# Power3V3.net
KiCad netlist of a schematic drawn in Altium Designer
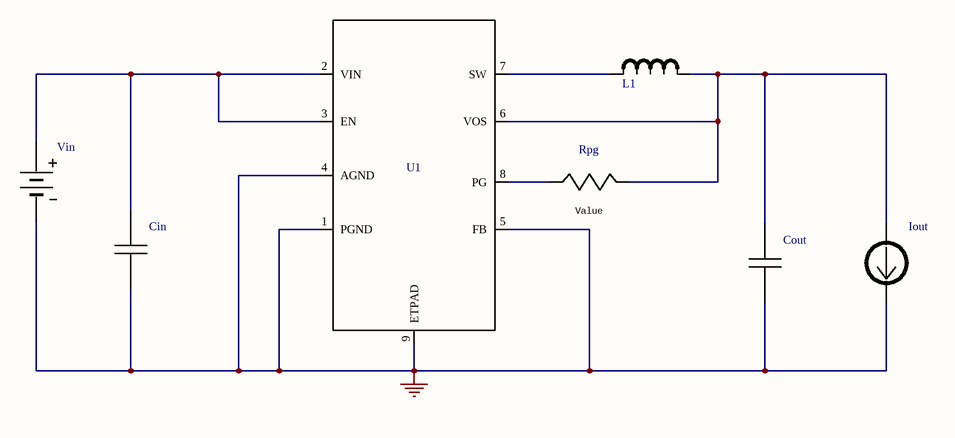
[diagram p0: Power3V3.SchDoc]

(export (version "E")
  (design (tool "Eeschema 10.0.6"))
  (components
    (comp (ref "Cin")
      (value "GRM219R61E106KA1")
      (footprint "0805")
      (description "Imported")
      (fields (field (name "MANUFACTURER_PART_NUMBER") "GRM219R61E106KA12"))
      (libsource (lib "TI WEBENCH") (part "GRM219R61E106KA1"))
    )
    (comp (ref "Cout")
      (value "GRM31CR70J226KE1")
      (footprint "1206")
      (description "Imported")
      (fields (field (name "MANUFACTURER_PART_NUMBER") "GRM31CR70J226KE19L"))
      (libsource (lib "TI WEBENCH") (part "GRM31CR70J226KE1"))
    )
    (comp (ref "Iout")
      (value "WB_CURRENT_LOAD")
      (description "Imported")
      (libsource (lib "TI WEBENCH") (part "WB_CURRENT_LOAD"))
    )
    (comp (ref "L1")
      (value "VLF252015MT-2R2M")
      (footprint "VLF252015MT")
      (description "Imported")
      (fields (field (name "MANUFACTURER_PART_NUMBER") "'VLF252015MT-2R2M'"))
      (libsource (lib "TI WEBENCH") (part "VLF252015MT-2R2M"))
    )
    (comp (ref "Rpg")
      (value "Value")
      (footprint "0402")
      (description "Imported")
      (fields (field (name "MANUFACTURER_PART_NUMBER") "CRCW0402100KFKED"))
      (libsource (lib "TI WEBENCH") (part "CRCW0402100KFKED"))
    )
    (comp (ref "U1")
      (value "TPS62172DSGR")
      (footprint "S-PWSON-N8")
      (description "Imported")
      (libsource (lib "TI WEBENCH") (part "TPS62172DSGR"))
    )
    (comp (ref "Vin")
      (value "WB_BATTERY")
      (description "Imported")
      (libsource (lib "TI WEBENCH") (part "WB_BATTERY"))
    )
  )
  (nets
    (net (code "1") (name "0") (class "Default")
      (node (ref "Cin") (pin "2") (pinfunction "2_2") (pintype "passive"))
      (node (ref "Cout") (pin "2") (pinfunction "2_2") (pintype "passive"))
      (node (ref "Iout") (pin "2") (pinfunction "-_2") (pintype "passive"))
      (node (ref "U1") (pin "1") (pinfunction "PGND_1") (pintype "passive"))
      (node (ref "U1") (pin "4") (pinfunction "AGND_4") (pintype "passive"))
      (node (ref "U1") (pin "5") (pinfunction "FB_5") (pintype "passive"))
      (node (ref "U1") (pin "9") (pinfunction "ETPAD_9") (pintype "passive"))
      (node (ref "Vin") (pin "2") (pinfunction "-_2") (pintype "passive"))
    )
    (net (code "2") (name "Net-(Iout-+)") (class "Default")
      (node (ref "Cout") (pin "1") (pinfunction "1_1") (pintype "passive"))
      (node (ref "Iout") (pin "1") (pinfunction "+_1") (pintype "passive"))
      (node (ref "L1") (pin "1") (pinfunction "1_1") (pintype "passive"))
      (node (ref "Rpg") (pin "1") (pinfunction "1_1") (pintype "passive"))
      (node (ref "U1") (pin "6") (pinfunction "VOS_6") (pintype "passive"))
    )
    (net (code "3") (name "Net-(U1-EN)") (class "Default")
      (node (ref "Cin") (pin "1") (pinfunction "1_1") (pintype "passive"))
      (node (ref "U1") (pin "2") (pinfunction "VIN_2") (pintype "passive"))
      (node (ref "U1") (pin "3") (pinfunction "EN_3") (pintype "passive"))
      (node (ref "Vin") (pin "1") (pinfunction "+_1") (pintype "passive"))
    )
    (net (code "4") (name "Net-(U1-PG)") (class "Default")
      (node (ref "Rpg") (pin "2") (pinfunction "2_2") (pintype "passive"))
      (node (ref "U1") (pin "8") (pinfunction "PG_8") (pintype "passive"))
    )
    (net (code "5") (name "Net-(U1-SW)") (class "Default")
      (node (ref "L1") (pin "2") (pinfunction "2_2") (pintype "passive"))
      (node (ref "U1") (pin "7") (pinfunction "SW_7") (pintype "passive"))
    )
  )
)
